# efr32_radio_interface.net
KiCad netlist of a schematic drawn in Altium Designer
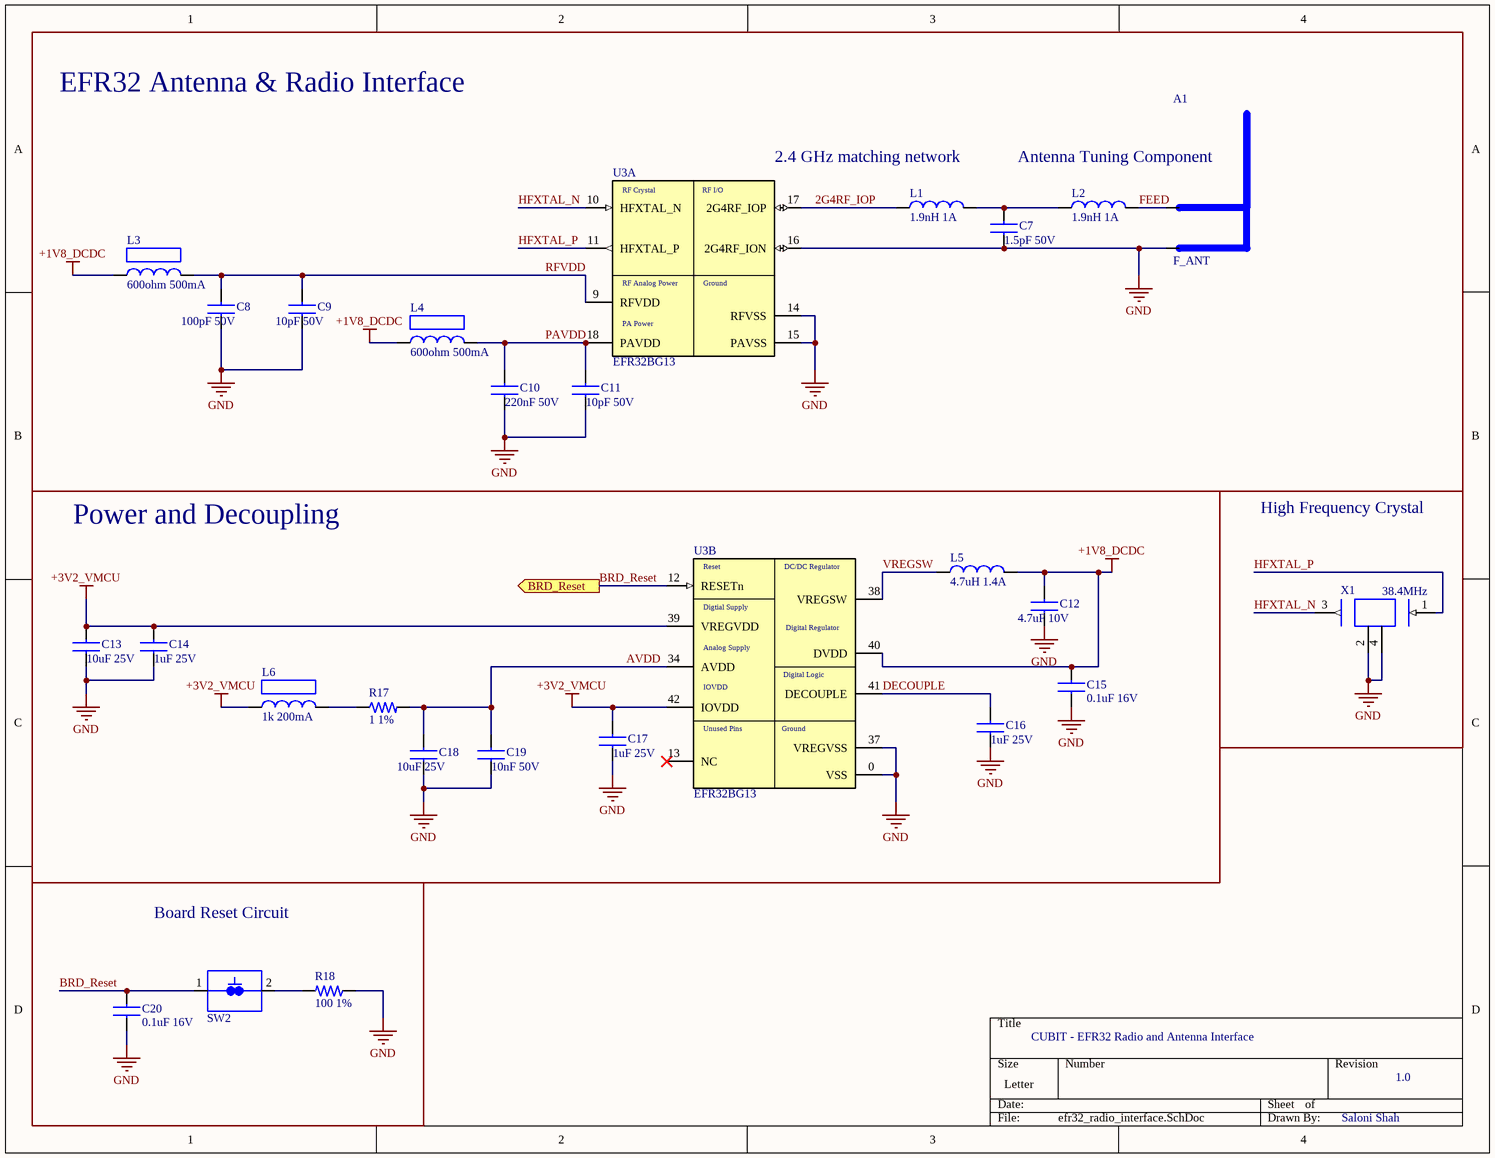
[diagram p0: efr32_radio_interface.SchDoc]

(export (version "E")
  (design (tool "Eeschema 10.0.6"))
  (components
    (comp (ref "A1")
      (value "F_ANT")
      (footprint "F_ANTENNA_FOOTPRINT")
      (libsource (lib "LPEDT_proj_lib") (part "F_ANT"))
    )
    (comp (ref "C7")
      (value "1.5pF 50V")
      (footprint "CAP_0402_1mm")
      (description "Cap Ceramic 1.5pF 50V C0G 5% Pad SMD 0402 125C Automotive T/R")
      (fields
        (field (name "MANUFACTURER") "Murata")
        (field (name "MANUFACTURER PART NUMBER") "GCM1555C1H1R5JA16D")
      )
      (libsource (lib "LPEDT_proj_lib") (part "GCM1555C1H1R5JA16D"))
    )
    (comp (ref "C8")
      (value "100pF 50V")
      (footprint "CAP_0805_02X125")
      (description "Cap 0.1nF ±10% 50V X7R 0805")
      (fields
        (field (name "MANUFACTURER") "Yageo")
        (field (name "MANUFACTURER PART NUMBER") "CC0805KRX7R9BB101")
      )
      (libsource (lib "LPEDT_proj_lib") (part "CC0805KRX7R9BB101"))
    )
    (comp (ref "C9")
      (value "10pF 50V")
      (footprint "CAP_0805_02X125")
      (description "Cap Ceramic 10pF 50V X7R 10% SMD 0805 125°C Paper T/R")
      (fields
        (field (name "MANUFACTURER") "KEMET")
        (field (name "MANUFACTURER PART NUMBER") "C0805C100K5RACTU")
      )
      (libsource (lib "LPEDT_proj_lib") (part "C0805C100K5RACTU"))
    )
    (comp (ref "C10")
      (value "220nF 50V")
      (footprint "CAP_0805_02X125")
      (description "Cap 220nF ±10% 50V X7R 0805")
      (fields
        (field (name "MANUFACTURER") "Yageo")
        (field (name "MANUFACTURER PART NUMBER") "CC0805KKX7R9BB224")
      )
      (libsource (lib "LPEDT_proj_lib") (part "CC0805KKX7R9BB224"))
    )
    (comp (ref "C11")
      (value "10pF 50V")
      (footprint "CAP_0805_02X125")
      (description "Cap Ceramic 10pF 50V X7R 10% SMD 0805 125°C Paper T/R")
      (fields
        (field (name "MANUFACTURER") "KEMET")
        (field (name "MANUFACTURER PART NUMBER") "C0805C100K5RACTU")
      )
      (libsource (lib "LPEDT_proj_lib") (part "C0805C100K5RACTU"))
    )
    (comp (ref "C12")
      (value "4.7uF 10V")
      (footprint "CAP_0603_1MM")
      (description "Cap CL10 Series 4.7 uF 10 V ±10 % Tolerance X5R SMT Multilayer Ceramic Capacitor")
      (fields
        (field (name "MANUFACTURER") "Samsung")
        (field (name "MANUFACTURER PART NUMBER") "CL10A475KP8NNNC")
      )
      (libsource (lib "LPEDT_proj_lib") (part "CL10A475KP8NNNC"))
    )
    (comp (ref "C13")
      (value "10uF 25V")
      (footprint "CAP_0805_02X125")
      (description "Cap 0805 25 V 10 uF ±20% Tolerance X5R Monolithic Ceramic Chip Capacitor")
      (fields
        (field (name "MANUFACTURER") "Murata")
        (field (name "MANUFACTURER PART NUMBER") "GRM21BR61E106KA73K")
      )
      (libsource (lib "LPEDT_proj_lib") (part "GRM21BR61E106KA73K"))
    )
    (comp (ref "C14")
      (value "1uF 25V")
      (footprint "CAP_0805_02X125")
      (description "Cap 1 µF ±10% 25V Ceramic Capacitor X5R 0805 (2012 Metric)")
      (fields
        (field (name "MANUFACTURER") "Murata")
        (field (name "MANUFACTURER PART NUMBER") "GRM216R61E105KA12D")
      )
      (libsource (lib "LPEDT_proj_lib") (part "GRM216R61E105KA12D"))
    )
    (comp (ref "C15")
      (value "0.1uF 16V")
      (footprint "CAP_0603_1MM")
      (description "Cap Ceramic 0.1uF 16V X7R 10% SMD 0603 125°C Paper T/R")
      (fields
        (field (name "MANUFACTURER") "KEMET")
        (field (name "MANUFACTURER PART NUMBER") "C0805C104K4RACAUTO")
      )
      (libsource (lib "LPEDT_proj_lib") (part "C0805C104K4RACAUTO"))
    )
    (comp (ref "C16")
      (value "1uF 25V")
      (footprint "CAP_0805_02X125")
      (description "Cap 1 µF ±10% 25V Ceramic Capacitor X5R 0805 (2012 Metric)")
      (fields
        (field (name "MANUFACTURER") "Murata")
        (field (name "MANUFACTURER PART NUMBER") "GRM216R61E105KA12D")
      )
      (libsource (lib "LPEDT_proj_lib") (part "GRM216R61E105KA12D"))
    )
    (comp (ref "C17")
      (value "1uF 25V")
      (footprint "CAP_0805_02X125")
      (description "Cap 1 µF ±10% 25V Ceramic Capacitor X5R 0805 (2012 Metric)")
      (fields
        (field (name "MANUFACTURER") "Murata")
        (field (name "MANUFACTURER PART NUMBER") "GRM216R61E105KA12D")
      )
      (libsource (lib "LPEDT_proj_lib") (part "GRM216R61E105KA12D"))
    )
    (comp (ref "C18")
      (value "10uF 25V")
      (footprint "CAP_0805_02X125")
      (description "Cap 0805 25 V 10 uF ±20% Tolerance X5R Monolithic Ceramic Chip Capacitor")
      (fields
        (field (name "MANUFACTURER") "Murata")
        (field (name "MANUFACTURER PART NUMBER") "GRM21BR61E106KA73K")
      )
      (libsource (lib "LPEDT_proj_lib") (part "GRM21BR61E106KA73K"))
    )
    (comp (ref "C19")
      (value "10nF 50V")
      (footprint "CAP_0805_02X125")
      (description "Cap 10nF ±10% 50V X7R 0805")
      (fields
        (field (name "MANUFACTURER") "Samsung")
        (field (name "MANUFACTURER PART NUMBER") "CL21B103KBCNNNC")
      )
      (libsource (lib "LPEDT_proj_lib") (part "CL21B103KBCNNNC"))
    )
    (comp (ref "C20")
      (value "0.1uF 16V")
      (footprint "CAP_0603_1MM")
      (description "Cap Ceramic 0.1uF 16V X7R 10% SMD 0603 125°C Paper T/R")
      (fields
        (field (name "MANUFACTURER") "KEMET")
        (field (name "MANUFACTURER PART NUMBER") "C0805C104K4RACAUTO")
      )
      (libsource (lib "LPEDT_proj_lib") (part "C0805C104K4RACAUTO"))
    )
    (comp (ref "L1")
      (value "1.9nH 1A")
      (footprint "CAP_0402_1mm")
      (description "Inductor Chip 1.9nH 0.3nH Tolerance 2-Pin 0402 Paper T/R")
      (fields
        (field (name "MANUFACTURER") "Murata")
        (field (name "MANUFACTURER PART NUMBER") "LQG15WZ1N9S02D")
      )
      (libsource (lib "LPEDT_proj_lib") (part "LQG15WZ1N9S02D"))
    )
    (comp (ref "L2")
      (value "1.9nH 1A")
      (footprint "CAP_0402_1mm")
      (description "Inductor Chip 1.9nH 0.3nH Tolerance 2-Pin 0402 Paper T/R")
      (fields
        (field (name "MANUFACTURER") "Murata")
        (field (name "MANUFACTURER PART NUMBER") "LQG15WZ1N9S02D")
      )
      (libsource (lib "LPEDT_proj_lib") (part "LQG15WZ1N9S02D"))
    )
    (comp (ref "L3")
      (value "600ohm 500mA")
      (footprint "IND_FERRITE_0603_1.6x0.4")
      (description "Ferrite Beads 0603 600Ω ±25% DCR=0.38Ω 500mA")
      (fields
        (field (name "MANUFACTURER") "Murata")
        (field (name "MANUFACTURER PART NUMBER") "BLM18AG601SN1D")
      )
      (libsource (lib "LPEDT_proj_lib") (part "BLM18AG601SN1D"))
    )
    (comp (ref "L4")
      (value "600ohm 500mA")
      (footprint "IND_FERRITE_0603_1.6x0.4")
      (description "Ferrite Beads 0603 600Ω ±25% DCR=0.38Ω 500mA")
      (fields
        (field (name "MANUFACTURER") "Murata")
        (field (name "MANUFACTURER PART NUMBER") "BLM18AG601SN1D")
      )
      (libsource (lib "LPEDT_proj_lib") (part "BLM18AG601SN1D"))
    )
    (comp (ref "L5")
      (value "4.7uH 1.4A")
      (footprint "INDP2523X23N_4u7")
      (description "4.7uH, 20%, 1 Element, Metal Alloy-Core, SMD, 1008")
      (fields
        (field (name "MANUFACTURER") "Murata")
        (field (name "MANUFACTURER PART NUMBER") "DFE252012P-4R7M=P2")
      )
      (libsource (lib "LPEDT_proj_lib") (part "DFE252012P-4R7M=P2"))
    )
    (comp (ref "L6")
      (value "1k 200mA")
      (footprint "CAP_0603_1MM")
      (description "Ferrite Beads WE-CBF 0603 SMD Bead 100MHz 1000Ohm 200mA")
      (fields
        (field (name "MANUFACTURER") "Wurth Electronics")
        (field (name "MANUFACTURER PART NUMBER") "74279266")
      )
      (libsource (lib "LPEDT_proj_lib") (part "74279266"))
    )
    (comp (ref "R17")
      (value "1 1%")
      (footprint "CAP_0603_1MM")
      (description "Res 1 Ohm 1% 1/10W ±200ppm/°C Molded SMD SMD Paper T/R")
      (fields
        (field (name "MANUFACTURER") "Yageo")
        (field (name "MANUFACTURER PART NUMBER") "RC0603FR-101RL")
      )
      (libsource (lib "LPEDT_proj_lib") (part "RC0603FR-101RL"))
    )
    (comp (ref "R18")
      (value "100 1%")
      (footprint "2_Chip_0603_RMCF")
      (description "Res 100 Ohm 1% 1/10W ±100ppm/°C Molded SMD SMD Paper T/R")
      (fields
        (field (name "MANUFACTURER") "Stackpole Electronics")
        (field (name "MANUFACTURER PART NUMBER") "RMCF0603FT100R")
      )
      (libsource (lib "LPEDT_proj_lib") (part "RMCF0603FT100R"))
    )
    (comp (ref "SW2")
      (value "Switch")
      (footprint "Reset Sw")
      (fields
        (field (name "MANUFACTURER") "ITT C&K")
        (field (name "MANUFACTURER PART NUMBER") "PTS636SL43SMTRLFS")
      )
      (libsource (lib "LPEDT_proj_lib") (part "PTS636SL43SMTRLFS"))
    )
    (comp (ref "U3")
      (value "EFR32BG13")
      (footprint "48-QFN_7x7")
      (description "Blue Gecko QFN48 2.4 G 19 dB BLE/Proprietary 512 kB 64 kB(RAM) 31GPIO")
      (fields
        (field (name "MANUFACTURER") "Silicon Labs")
        (field (name "MANUFACTURER PART NUMBER") "EFR32BG13P732F512GM48-D")
      )
      (libsource (lib "LPEDT_proj_lib") (part "EFR32BG13P732F512GM48-D"))
    )
    (comp (ref "X1")
      (value "38.4MHz")
      (footprint "OSC_38.4MHz")
      (description "Crystal 38.4000MHZ 10PF SMD")
      (fields
        (field (name "MANUFACTURER") "Raltron Electronics")
        (field (name "MANUFACTURER PART NUMBER") "RH100-38.400-10-F-1010-TR")
      )
      (libsource (lib "LPEDT_proj_lib") (part "RH100-38.400-10-F-1010-TR"))
    )
  )
  (nets
    (net (code "1") (name "+1V8_DCDC") (class "Default")
      (node (ref "C12") (pin "1") (pinfunction "1_1") (pintype "passive"))
      (node (ref "C15") (pin "1") (pinfunction "1_1") (pintype "passive"))
      (node (ref "L3") (pin "1") (pinfunction "1_1") (pintype "passive"))
      (node (ref "L4") (pin "1") (pinfunction "1_1") (pintype "passive"))
      (node (ref "L5") (pin "2") (pinfunction "2_2") (pintype "passive"))
      (node (ref "U3") (pin "40") (pinfunction "DVDD_40") (pintype "power_in"))
    )
    (net (code "2") (name "+3V2_VMCU") (class "Default")
      (node (ref "C13") (pin "1") (pinfunction "1_1") (pintype "passive"))
      (node (ref "C14") (pin "1") (pinfunction "1_1") (pintype "passive"))
      (node (ref "C17") (pin "1") (pinfunction "1_1") (pintype "passive"))
      (node (ref "L6") (pin "1") (pinfunction "1_1") (pintype "passive"))
      (node (ref "U3") (pin "39") (pinfunction "VREGVDD_39") (pintype "power_in"))
      (node (ref "U3") (pin "42") (pinfunction "IOVDD_42") (pintype "power_in"))
    )
    (net (code "3") (name "/2G4RF_IOP") (class "Default")
      (node (ref "L1") (pin "1") (pinfunction "1_1") (pintype "passive"))
      (node (ref "U3") (pin "17") (pinfunction "2G4RF_IOP_17") (pintype "bidirectional"))
    )
    (net (code "4") (name "/AVDD") (class "Default")
      (node (ref "C18") (pin "1") (pinfunction "1_1") (pintype "passive"))
      (node (ref "C19") (pin "1") (pinfunction "1_1") (pintype "passive"))
      (node (ref "R17") (pin "2") (pinfunction "2_2") (pintype "passive"))
      (node (ref "U3") (pin "34") (pinfunction "AVDD_34") (pintype "power_in"))
    )
    (net (code "5") (name "/BRD_Reset") (class "Default")
      (node (ref "C20") (pin "1") (pinfunction "1_1") (pintype "passive"))
      (node (ref "SW2") (pin "1") (pinfunction "1_1") (pintype "passive"))
      (node (ref "U3") (pin "12") (pinfunction "RESETn_12") (pintype "input"))
    )
    (net (code "6") (name "/DECOUPLE") (class "Default")
      (node (ref "C16") (pin "1") (pinfunction "1_1") (pintype "passive"))
      (node (ref "U3") (pin "41") (pinfunction "DECOUPLE_41") (pintype "power_in"))
    )
    (net (code "7") (name "/FEED") (class "Default")
      (node (ref "A1") (pin "FEED") (pinfunction "FEED_FEED") (pintype "passive"))
      (node (ref "L2") (pin "2") (pinfunction "2_2") (pintype "passive"))
    )
    (net (code "8") (name "/HFXTAL_N") (class "Default")
      (node (ref "U3") (pin "10") (pinfunction "HFXTAL_N_10") (pintype "input"))
      (node (ref "X1") (pin "3") (pintype "output"))
    )
    (net (code "9") (name "/HFXTAL_P") (class "Default")
      (node (ref "U3") (pin "11") (pinfunction "HFXTAL_P_11") (pintype "output"))
      (node (ref "X1") (pin "1") (pintype "input"))
    )
    (net (code "10") (name "/PAVDD") (class "Default")
      (node (ref "C10") (pin "1") (pinfunction "1_1") (pintype "passive"))
      (node (ref "C11") (pin "1") (pinfunction "1_1") (pintype "passive"))
      (node (ref "L4") (pin "2") (pinfunction "2_2") (pintype "passive"))
      (node (ref "U3") (pin "18") (pinfunction "PAVDD_18") (pintype "power_in"))
    )
    (net (code "11") (name "/RFVDD") (class "Default")
      (node (ref "C8") (pin "1") (pinfunction "1_1") (pintype "passive"))
      (node (ref "C9") (pin "1") (pinfunction "1_1") (pintype "passive"))
      (node (ref "L3") (pin "2") (pinfunction "2_2") (pintype "passive"))
      (node (ref "U3") (pin "9") (pinfunction "RFVDD_9") (pintype "power_in"))
    )
    (net (code "12") (name "/VREGSW") (class "Default")
      (node (ref "L5") (pin "1") (pinfunction "1_1") (pintype "passive"))
      (node (ref "U3") (pin "38") (pinfunction "VREGSW_38") (pintype "power_in"))
    )
    (net (code "13") (name "GND") (class "Default")
      (node (ref "A1") (pin "GND") (pinfunction "GND_GND") (pintype "passive"))
      (node (ref "C10") (pin "2") (pinfunction "2_2") (pintype "passive"))
      (node (ref "C11") (pin "2") (pinfunction "2_2") (pintype "passive"))
      (node (ref "C12") (pin "2") (pinfunction "2_2") (pintype "passive"))
      (node (ref "C13") (pin "2") (pinfunction "2_2") (pintype "passive"))
      (node (ref "C14") (pin "2") (pinfunction "2_2") (pintype "passive"))
      (node (ref "C15") (pin "2") (pinfunction "2_2") (pintype "passive"))
      (node (ref "C16") (pin "2") (pinfunction "2_2") (pintype "passive"))
      (node (ref "C17") (pin "2") (pinfunction "2_2") (pintype "passive"))
      (node (ref "C18") (pin "2") (pinfunction "2_2") (pintype "passive"))
      (node (ref "C19") (pin "2") (pinfunction "2_2") (pintype "passive"))
      (node (ref "C20") (pin "2") (pinfunction "2_2") (pintype "passive"))
      (node (ref "C7") (pin "2") (pinfunction "2_2") (pintype "passive"))
      (node (ref "C8") (pin "2") (pinfunction "2_2") (pintype "passive"))
      (node (ref "C9") (pin "2") (pinfunction "2_2") (pintype "passive"))
      (node (ref "R18") (pin "1") (pinfunction "1_1") (pintype "passive"))
      (node (ref "U3") (pin "0") (pinfunction "VSS_0") (pintype "power_in"))
      (node (ref "U3") (pin "14") (pinfunction "RFVSS_14") (pintype "power_in"))
      (node (ref "U3") (pin "15") (pinfunction "PAVSS_15") (pintype "power_in"))
      (node (ref "U3") (pin "16") (pinfunction "2G4RF_ION_16") (pintype "bidirectional"))
      (node (ref "U3") (pin "37") (pinfunction "VREGVSS_37") (pintype "power_in"))
      (node (ref "X1") (pin "2") (pintype "power_in"))
      (node (ref "X1") (pin "4") (pintype "power_in"))
    )
    (net (code "14") (name "Net-(C7-Pad1)") (class "Default")
      (node (ref "C7") (pin "1") (pinfunction "1_1") (pintype "passive"))
      (node (ref "L1") (pin "2") (pinfunction "2_2") (pintype "passive"))
      (node (ref "L2") (pin "1") (pinfunction "1_1") (pintype "passive"))
    )
    (net (code "15") (name "Net-(L6-Pad2)") (class "Default")
      (node (ref "L6") (pin "2") (pinfunction "2_2") (pintype "passive"))
      (node (ref "R17") (pin "1") (pinfunction "1_1") (pintype "passive"))
    )
    (net (code "16") (name "Net-(R18-Pad2)") (class "Default")
      (node (ref "R18") (pin "2") (pinfunction "2_2") (pintype "passive"))
      (node (ref "SW2") (pin "2") (pinfunction "2_2") (pintype "passive"))
    )
    (net (code "17") (name "unconnected-(U3B-NC-Pad13)") (class "Default")
      (node (ref "U3") (pin "13") (pinfunction "NC_13") (pintype "passive+no_connect"))
    )
  )
)
